# bridge.net
KiCad netlist of a schematic drawn in Altium Designer
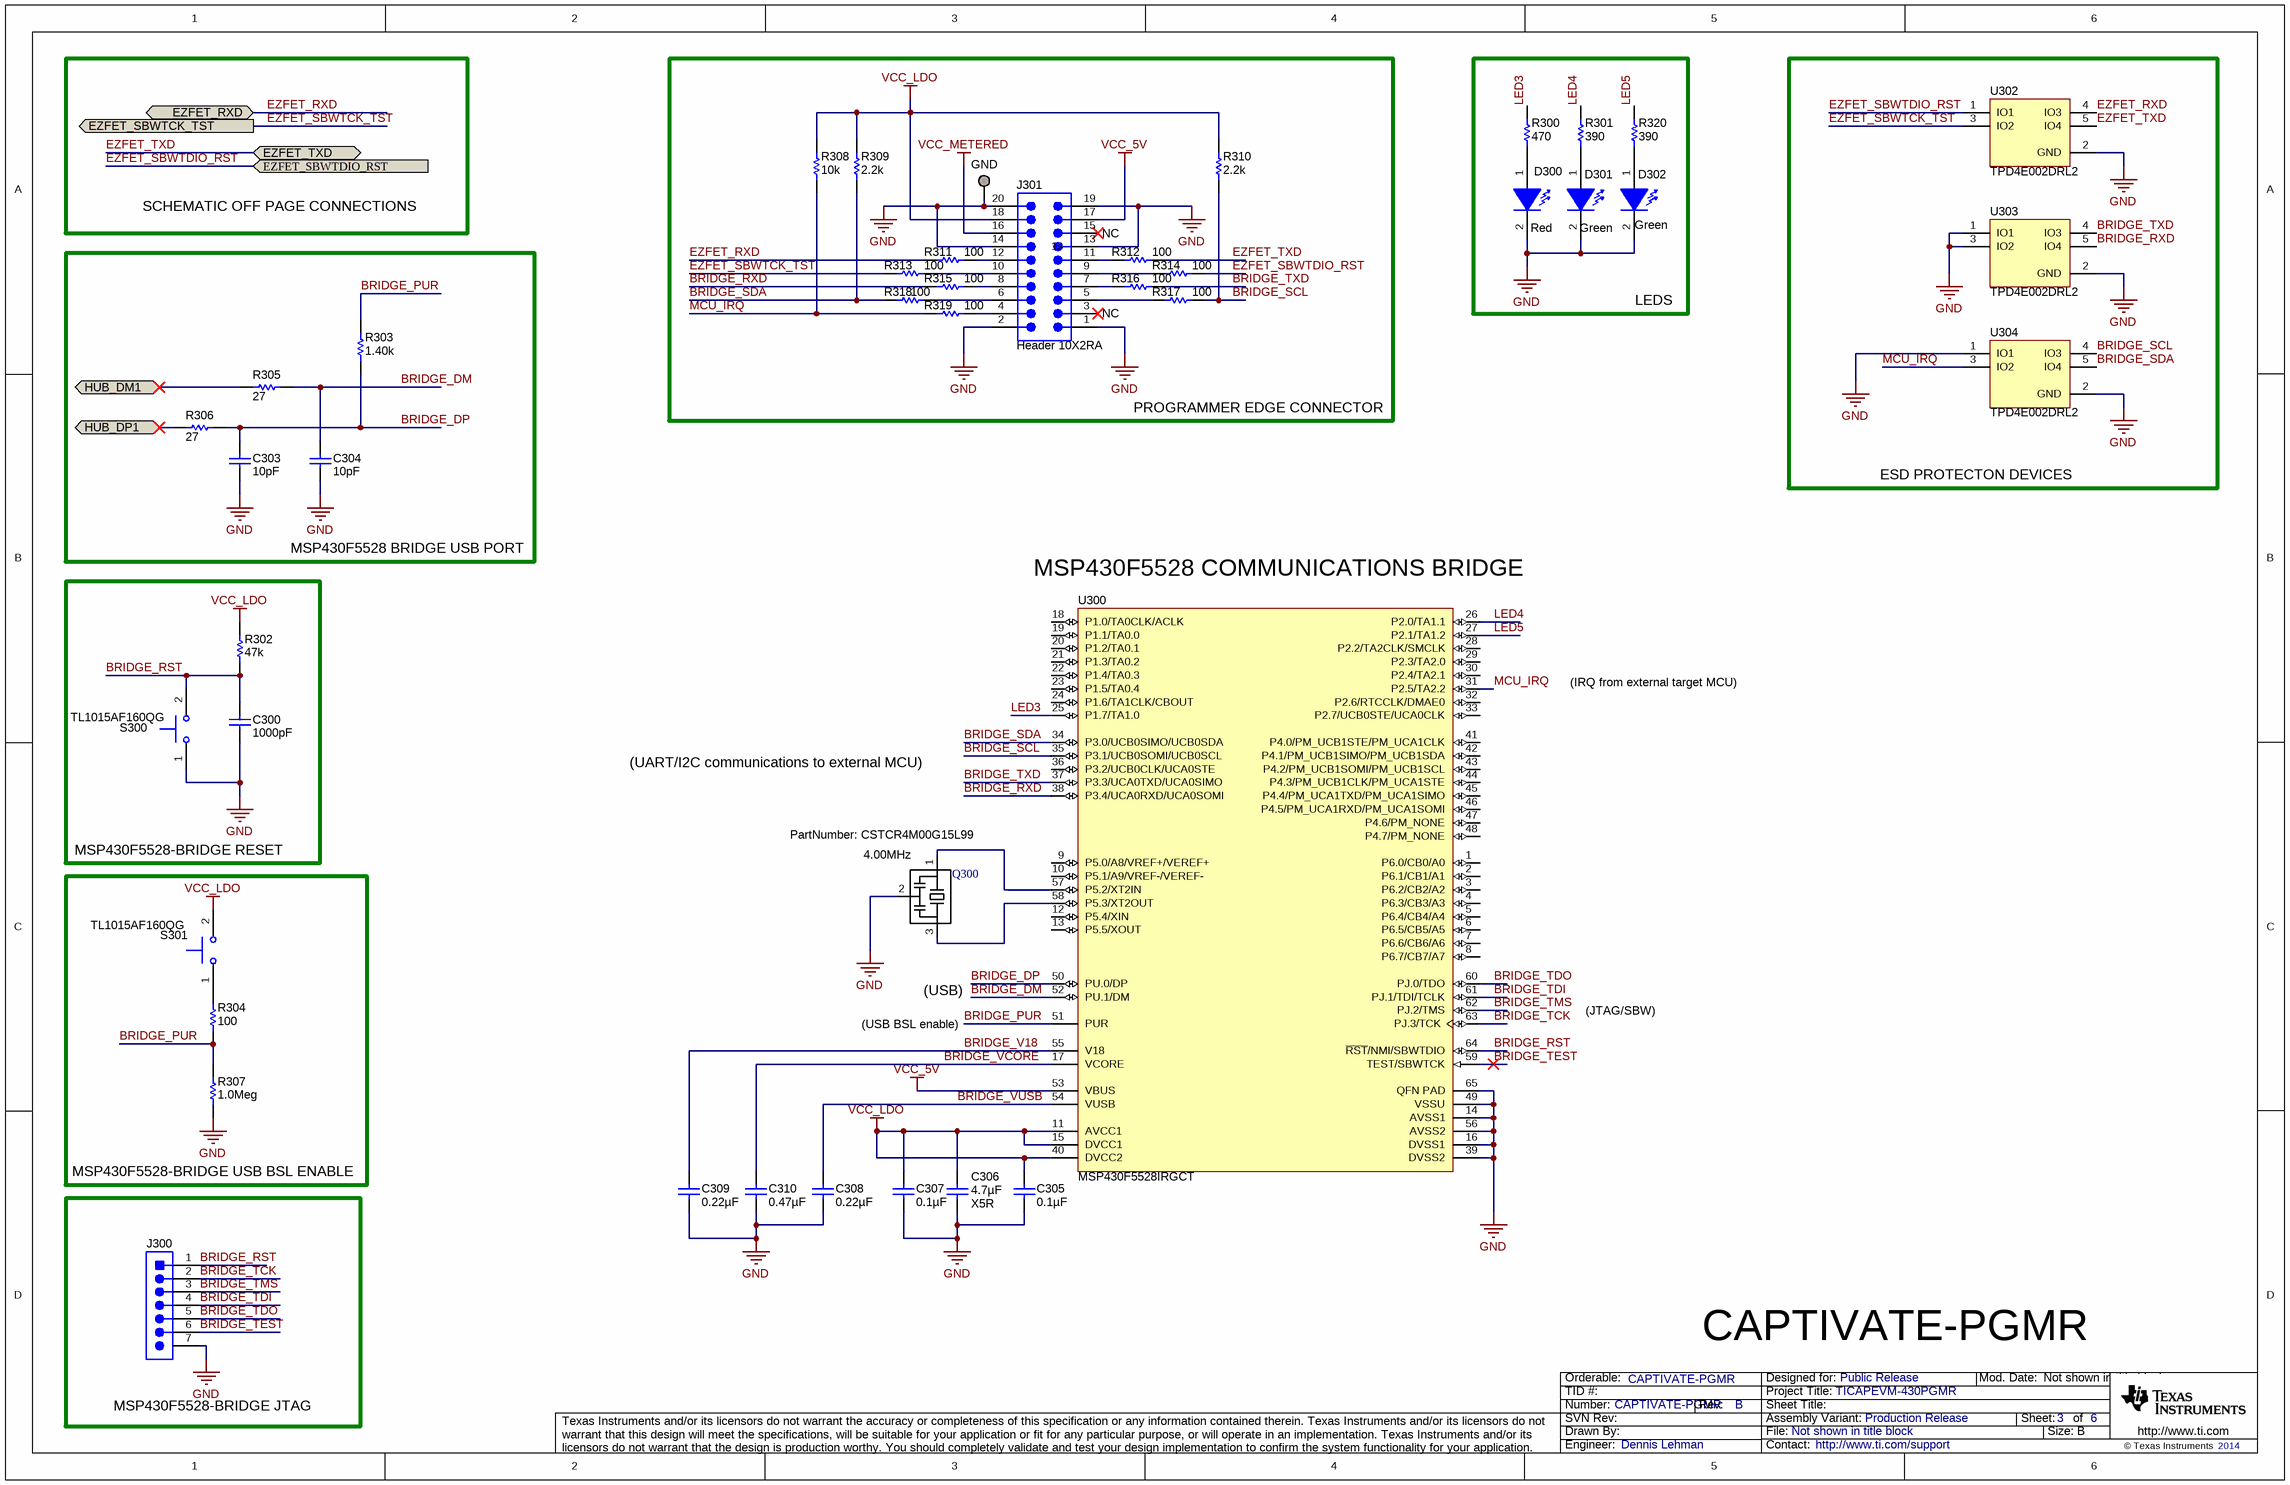
[diagram p0: bridge.SchDoc]

(export (version "E")
  (design (tool "Eeschema 10.0.6"))
  (components
    (comp (ref "C300")
      (value "C1005X7R1H102K")
      (footprint "0402")
      (description "CAP, CERM, 1000pF, 50V, +/-10%, X7R, 0402")
      (fields
        (field (name "VALUEDISPLAYED") "1000pF")
        (field (name "MANUFACTURER") "TDK")
        (field (name "PUBLISHER") "Texas Instruments")
      )
      (libsource (lib "Capacitor_Ceramic") (part "C1005X7R1H102K"))
    )
    (comp (ref "C303")
      (value "GRM1555C1H100JA01D")
      (footprint "0402")
      (description "CAP, CERM, 10pF, 50V, +/-5%, C0G/NP0, 0402")
      (fields
        (field (name "VALUEDISPLAYED") "10pF")
        (field (name "MANUFACTURER") "MuRata")
        (field (name "PUBLISHER") "Texas Instruments")
      )
      (libsource (lib "Capacitor_Ceramic") (part "GRM1555C1H100JA01D"))
    )
    (comp (ref "C304")
      (value "GRM1555C1H100JA01D")
      (footprint "0402")
      (description "CAP, CERM, 10pF, 50V, +/-5%, C0G/NP0, 0402")
      (fields
        (field (name "VALUEDISPLAYED") "10pF")
        (field (name "MANUFACTURER") "MuRata")
        (field (name "PUBLISHER") "Texas Instruments")
      )
      (libsource (lib "Capacitor_Ceramic") (part "GRM1555C1H100JA01D"))
    )
    (comp (ref "C305")
      (value "GRM155R61C104KA88D")
      (footprint "0402")
      (description "CAP, CERM, 0.1uF, 16V, +/-10%, X5R, 0402")
      (fields
        (field (name "VALUEDISPLAYED") "0.1µF")
        (field (name "MANUFACTURER") "MuRata")
        (field (name "PUBLISHER") "Texas Instruments")
      )
      (libsource (lib "Capacitor_Ceramic") (part "GRM155R61C104KA88D"))
    )
    (comp (ref "C306")
      (value "CGB3B1X5R1A475K055AC")
      (footprint "0603")
      (description "CAP, CERM, 4.7 µF, 10 V, +/- 10%, X5R, 0603")
      (fields
        (field (name "VALUEDISPLAYED") "4.7µF")
        (field (name "MANUFACTURER") "TDK")
        (field (name "TEMPCO") "X5R")
        (field (name "PUBLISHER") "Texas Instruments")
      )
      (libsource (lib "Capacitor_Ceramic") (part "CGB3B1X5R1A475K055AC"))
    )
    (comp (ref "C307")
      (value "GRM155R61C104KA88D")
      (footprint "0402")
      (description "CAP, CERM, 0.1uF, 16V, +/-10%, X5R, 0402")
      (fields
        (field (name "VALUEDISPLAYED") "0.1µF")
        (field (name "MANUFACTURER") "MuRata")
        (field (name "PUBLISHER") "Texas Instruments")
      )
      (libsource (lib "Capacitor_Ceramic") (part "GRM155R61C104KA88D"))
    )
    (comp (ref "C308")
      (value "GRM155R61A224KE19D")
      (footprint "0402")
      (description "CAP, CERM, 0.22uF, 10V, +/-10%, X5R, 0402")
      (fields
        (field (name "VALUEDISPLAYED") "0.22µF")
        (field (name "MANUFACTURER") "MuRata")
        (field (name "PUBLISHER") "Texas Instruments")
      )
      (libsource (lib "Capacitor_Ceramic") (part "GRM155R61A224KE19D"))
    )
    (comp (ref "C309")
      (value "GRM155R61A224KE19D")
      (footprint "0402")
      (description "CAP, CERM, 0.22uF, 10V, +/-10%, X5R, 0402")
      (fields
        (field (name "VALUEDISPLAYED") "0.22µF")
        (field (name "MANUFACTURER") "MuRata")
        (field (name "PUBLISHER") "Texas Instruments")
      )
      (libsource (lib "Capacitor_Ceramic") (part "GRM155R61A224KE19D"))
    )
    (comp (ref "C310")
      (value "GRM155R61A474KE15D")
      (footprint "0402")
      (description "CAP, CERM, 0.47uF, 10V, +/-10%, X5R, 0402")
      (fields
        (field (name "VALUEDISPLAYED") "0.47µF")
        (field (name "MANUFACTURER") "MuRata")
        (field (name "PUBLISHER") "Texas Instruments")
      )
      (libsource (lib "Capacitor_Ceramic") (part "GRM155R61A474KE15D"))
    )
    (comp (ref "D300")
      (value "Red")
      (footprint "LED_LTST-C190_Red")
      (description "LED, Red, SMD")
      (fields
        (field (name "MANUFACTURER") "Lite-On")
        (field (name "PARTNUMBER") "LTST-C190CKT")
        (field (name "PUBLISHER") "Texas Instruments")
      )
      (libsource (lib "LED") (part "LTST-C190CKT"))
    )
    (comp (ref "D301")
      (value "Green")
      (footprint "LED_LTST-C190")
      (description "LED, Green, SMD")
      (fields
        (field (name "MANUFACTURER") "Lite-On")
        (field (name "PARTNUMBER") "LTST-C190GKT")
        (field (name "PUBLISHER") "Texas Instruments")
      )
      (libsource (lib "LED") (part "LTST-C190GKT"))
    )
    (comp (ref "D302")
      (value "Green")
      (footprint "LED_LTST-C190")
      (description "LED, Green, SMD")
      (fields
        (field (name "MANUFACTURER") "Lite-On")
        (field (name "PARTNUMBER") "LTST-C190GKT")
        (field (name "PUBLISHER") "Texas Instruments")
      )
      (libsource (lib "LED") (part "LTST-C190GKT"))
    )
    (comp (ref "GND")
      (value "TESTPOINT")
      (footprint "TP_VIA_060RND040")
      (description "TEST POINT.  No entry in BOM.")
      (fields (field (name "PUBLISHER") "Texas Instruments"))
      (libsource (lib "MiscParts") (part "TESTPOINT"))
    )
    (comp (ref "J300")
      (value "GRPB071VWVN-RC")
      (footprint "Sullins_GRPB071VWVN-RC")
      (description "Header, 50mil, 7x1, Gold,  TH")
      (fields
        (field (name "MANUFACTURER") "Sullins Connector Solutions")
        (field (name "PUBLISHER") "Texas Instruments")
      )
      (libsource (lib "Captivate Library") (part "GRPB071VWVN-RC"))
    )
    (comp (ref "J301")
      (value "Header 10X2RA")
      (footprint "HDR2X10RA")
      (description "Header, Male, 10-Pin, 2 row, Shround, Right Angle")
      (fields
        (field (name "MANUFACTURER") "Samtec")
        (field (name "PARTNUMBER") "TSSH-110-01-L-D-RA")
        (field (name "PUBLISHER") "Altium Limited")
      )
      (libsource (lib "Captivate Library") (part "Header 10X2RA"))
    )
    (comp (ref "Q300")
      (value "RATA-FILTER_CSTCR4M00G15")
      (footprint "CSTCR CERAMIC RESONATOR - MURATA")
      (description "4.00MHz resonator")
      (fields (field (name "VALUE DISPLAYED") "4.00MHz") (field (name "PARTNUMBER") "CSTCR4M00G15L99"))
      (libsource (lib "Captivate Library") (part "MURATA-FILTER_CSTCR4M00G15"))
    )
    (comp (ref "R300")
      (value "470")
      (footprint "0402")
      (description "RES, 470 ohm, 5%, 0.063W, 0402")
      (fields
        (field (name "PARTNUMBER") "CRCW0402470RJNED")
        (field (name "MANUFACTURER") "Vishay-Dale")
        (field (name "PUBLISHER") "Texas Instruments")
      )
      (libsource (lib "Resistor_0402") (part "CRCW0402470RJNED"))
    )
    (comp (ref "R301")
      (value "390")
      (footprint "0402")
      (description "RES, 390 ohm, 5%, 0.063W, 0402")
      (fields
        (field (name "PARTNUMBER") "CRCW0402390RJNED")
        (field (name "MANUFACTURER") "Vishay-Dale")
        (field (name "PUBLISHER") "Texas Instruments")
      )
      (libsource (lib "Resistor_0402") (part "CRCW0402390RJNED"))
    )
    (comp (ref "R302")
      (value "47k")
      (footprint "0402")
      (description "RES, 47k ohm, 5%, 0.063W, 0402")
      (fields
        (field (name "PARTNUMBER") "CRCW040247K0JNED")
        (field (name "MANUFACTURER") "Vishay-Dale")
        (field (name "PUBLISHER") "Texas Instruments")
      )
      (libsource (lib "Resistor_0402") (part "CRCW040247K0JNED"))
    )
    (comp (ref "R303")
      (value "1.40k")
      (footprint "0402")
      (description "RES, 1.40k ohm, 1%, 0.063W, 0402")
      (fields
        (field (name "PARTNUMBER") "CRCW04021K40FKED")
        (field (name "MANUFACTURER") "Vishay-Dale")
        (field (name "PUBLISHER") "Texas Instruments")
      )
      (libsource (lib "Resistor_0402") (part "CRCW04021K40FKED"))
    )
    (comp (ref "R304")
      (value "100")
      (footprint "0402")
      (description "RES, 100 ohm, 5%, 0.063W, 0402")
      (fields
        (field (name "PARTNUMBER") "CRCW0402100RJNED")
        (field (name "MANUFACTURER") "Vishay-Dale")
        (field (name "PUBLISHER") "Texas Instruments")
      )
      (libsource (lib "Resistor_0402") (part "CRCW0402100RJNED"))
    )
    (comp (ref "R305")
      (value "27")
      (footprint "0402")
      (description "RES, 27 ohm, 5%, 0.063W, 0402")
      (fields
        (field (name "PARTNUMBER") "CRCW040227R0JNED")
        (field (name "MANUFACTURER") "Vishay-Dale")
        (field (name "PUBLISHER") "Texas Instruments")
      )
      (libsource (lib "Resistor_0402") (part "CRCW040227R0JNED"))
    )
    (comp (ref "R306")
      (value "27")
      (footprint "0402")
      (description "RES, 27 ohm, 5%, 0.063W, 0402")
      (fields
        (field (name "PARTNUMBER") "CRCW040227R0JNED")
        (field (name "MANUFACTURER") "Vishay-Dale")
        (field (name "PUBLISHER") "Texas Instruments")
      )
      (libsource (lib "Resistor_0402") (part "CRCW040227R0JNED"))
    )
    (comp (ref "R307")
      (value "1.0Meg")
      (footprint "0402")
      (description "RES, 1.0Meg ohm, 5%, 0.063W, 0402")
      (fields
        (field (name "PARTNUMBER") "CRCW04021M00JNED")
        (field (name "MANUFACTURER") "Vishay-Dale")
        (field (name "PUBLISHER") "Texas Instruments")
      )
      (libsource (lib "Resistor_0402") (part "CRCW04021M00JNED"))
    )
    (comp (ref "R308")
      (value "CRCW040210K0JNED")
      (footprint "0402")
      (description "RES, 10 k, 5%, 0.063 W, 0402")
      (fields
        (field (name "VALUEDISPLAYED") "10k")
        (field (name "MANUFACTURER") "Vishay-Dale")
        (field (name "PUBLISHER") "Texas Instruments")
      )
      (libsource (lib "Resistor_0402") (part "CRCW040210K0JNED"))
    )
    (comp (ref "R309")
      (value "CRCW04022K20JNED")
      (footprint "0402")
      (description "RES, 2.2 k, 5%, 0.063 W, 0402")
      (fields
        (field (name "VALUEDISPLAYED") "2.2k")
        (field (name "MANUFACTURER") "Vishay-Dale")
        (field (name "PUBLISHER") "Texas Instruments")
      )
      (libsource (lib "Resistor_0402") (part "CRCW04022K20JNED"))
    )
    (comp (ref "R310")
      (value "CRCW04022K20JNED")
      (footprint "0402")
      (description "RES, 2.2 k, 5%, 0.063 W, 0402")
      (fields
        (field (name "VALUEDISPLAYED") "2.2k")
        (field (name "MANUFACTURER") "Vishay-Dale")
        (field (name "PUBLISHER") "Texas Instruments")
      )
      (libsource (lib "Resistor_0402") (part "CRCW04022K20JNED"))
    )
    (comp (ref "R311")
      (value "CRCW0402100RJNED")
      (footprint "0402")
      (description "RES, 100, 5%, 0.063 W, 0402")
      (fields
        (field (name "VALUEDISPLAYED") "100")
        (field (name "MANUFACTURER") "Vishay-Dale")
        (field (name "PUBLISHER") "Texas Instruments")
      )
      (libsource (lib "Resistor_0402") (part "CRCW0402100RJNED"))
    )
    (comp (ref "R312")
      (value "CRCW0402100RJNED")
      (footprint "0402")
      (description "RES, 100, 5%, 0.063 W, 0402")
      (fields
        (field (name "VALUEDISPLAYED") "100")
        (field (name "MANUFACTURER") "Vishay-Dale")
        (field (name "PUBLISHER") "Texas Instruments")
      )
      (libsource (lib "Resistor_0402") (part "CRCW0402100RJNED"))
    )
    (comp (ref "R313")
      (value "CRCW0402100RJNED")
      (footprint "0402")
      (description "RES, 100, 5%, 0.063 W, 0402")
      (fields
        (field (name "VALUEDISPLAYED") "100")
        (field (name "MANUFACTURER") "Vishay-Dale")
        (field (name "PUBLISHER") "Texas Instruments")
      )
      (libsource (lib "Resistor_0402") (part "CRCW0402100RJNED"))
    )
    (comp (ref "R314")
      (value "CRCW0402100RJNED")
      (footprint "0402")
      (description "RES, 100, 5%, 0.063 W, 0402")
      (fields
        (field (name "VALUEDISPLAYED") "100")
        (field (name "MANUFACTURER") "Vishay-Dale")
        (field (name "PUBLISHER") "Texas Instruments")
      )
      (libsource (lib "Resistor_0402") (part "CRCW0402100RJNED"))
    )
    (comp (ref "R315")
      (value "CRCW0402100RJNED")
      (footprint "0402")
      (description "RES, 100, 5%, 0.063 W, 0402")
      (fields
        (field (name "VALUEDISPLAYED") "100")
        (field (name "MANUFACTURER") "Vishay-Dale")
        (field (name "PUBLISHER") "Texas Instruments")
      )
      (libsource (lib "Resistor_0402") (part "CRCW0402100RJNED"))
    )
    (comp (ref "R316")
      (value "CRCW0402100RJNED")
      (footprint "0402")
      (description "RES, 100, 5%, 0.063 W, 0402")
      (fields
        (field (name "VALUEDISPLAYED") "100")
        (field (name "MANUFACTURER") "Vishay-Dale")
        (field (name "PUBLISHER") "Texas Instruments")
      )
      (libsource (lib "Resistor_0402") (part "CRCW0402100RJNED"))
    )
    (comp (ref "R317")
      (value "CRCW0402100RJNED")
      (footprint "0402")
      (description "RES, 100, 5%, 0.063 W, 0402")
      (fields
        (field (name "VALUEDISPLAYED") "100")
        (field (name "MANUFACTURER") "Vishay-Dale")
        (field (name "PUBLISHER") "Texas Instruments")
      )
      (libsource (lib "Resistor_0402") (part "CRCW0402100RJNED"))
    )
    (comp (ref "R318")
      (value "CRCW0402100RJNED")
      (footprint "0402")
      (description "RES, 100, 5%, 0.063 W, 0402")
      (fields
        (field (name "VALUEDISPLAYED") "100")
        (field (name "MANUFACTURER") "Vishay-Dale")
        (field (name "PUBLISHER") "Texas Instruments")
      )
      (libsource (lib "Resistor_0402") (part "CRCW0402100RJNED"))
    )
    (comp (ref "R319")
      (value "CRCW0402100RJNED")
      (footprint "0402")
      (description "RES, 100, 5%, 0.063 W, 0402")
      (fields
        (field (name "VALUEDISPLAYED") "100")
        (field (name "MANUFACTURER") "Vishay-Dale")
        (field (name "PUBLISHER") "Texas Instruments")
      )
      (libsource (lib "Resistor_0402") (part "CRCW0402100RJNED"))
    )
    (comp (ref "R320")
      (value "390")
      (footprint "0402")
      (description "RES, 390 ohm, 5%, 0.063W, 0402")
      (fields
        (field (name "PARTNUMBER") "CRCW0402390RJNED")
        (field (name "MANUFACTURER") "Vishay-Dale")
        (field (name "PUBLISHER") "Texas Instruments")
      )
      (libsource (lib "Resistor_0402") (part "CRCW0402390RJNED"))
    )
    (comp (ref "S300")
      (value "TL1015AF160QG")
      (footprint "SW_TL1015AF160QG")
      (description "Switch, Tactile, SPST-NO, 0.05A, 12V, SMT")
      (fields
        (field (name "MANUFACTURER") "E-Switch")
        (field (name "SYMBOLCREATOR") "a0412235")
        (field (name "PUBLISHER") "Texas Instruments")
      )
      (libsource (lib "Switches") (part "TL1015AF160QG"))
    )
    (comp (ref "S301")
      (value "TL1015AF160QG")
      (footprint "SW_TL1015AF160QG")
      (description "Switch, Tactile, SPST-NO, 0.05A, 12V, SMT")
      (fields
        (field (name "MANUFACTURER") "E-Switch")
        (field (name "SYMBOLCREATOR") "a0412235")
        (field (name "PUBLISHER") "Texas Instruments")
      )
      (libsource (lib "Switches") (part "TL1015AF160QG"))
    )
    (comp (ref "U300")
      (value "MSP430F5528IRGCT")
      (footprint "RGC0064B")
      (fields (field (name "MANUFACTURER") "Texas Instruments"))
      (libsource (lib "TI MCU MSP430") (part "MSP430F5528IRGCT"))
    )
    (comp (ref "U302")
      (value "TPD4E002DRL2")
      (footprint "DRL0005A")
      (fields
        (field (name "MANUFACTURER") "Texas Instruments")
        (field (name "ALTERNATE PARTNUMBER") "Equivalent")
      )
      (libsource (lib "TI Interface ESD EMI Protection") (part "TPD4E002DRL2"))
    )
    (comp (ref "U303")
      (value "TPD4E002DRL2")
      (footprint "DRL0005A")
      (fields
        (field (name "MANUFACTURER") "Texas Instruments")
        (field (name "ALTERNATE PARTNUMBER") "Equivalent")
      )
      (libsource (lib "TI Interface ESD EMI Protection") (part "TPD4E002DRL2"))
    )
    (comp (ref "U304")
      (value "TPD4E002DRL2")
      (footprint "DRL0005A")
      (fields
        (field (name "MANUFACTURER") "Texas Instruments")
        (field (name "ALTERNATE PARTNUMBER") "Equivalent")
      )
      (libsource (lib "TI Interface ESD EMI Protection") (part "TPD4E002DRL2"))
    )
  )
  (nets
    (net (code "1") (name "/BRIDGE_DM") (class "Default")
      (node (ref "C304") (pin "1") (pinfunction "1_1") (pintype "passive"))
      (node (ref "R305") (pin "2") (pinfunction "2_2") (pintype "passive"))
      (node (ref "U300") (pin "52") (pinfunction "PU.1/DM_52") (pintype "bidirectional"))
    )
    (net (code "2") (name "/BRIDGE_DP") (class "Default")
      (node (ref "C303") (pin "1") (pinfunction "1_1") (pintype "passive"))
      (node (ref "R303") (pin "1") (pinfunction "1_1") (pintype "passive"))
      (node (ref "R306") (pin "2") (pinfunction "2_2") (pintype "passive"))
      (node (ref "U300") (pin "50") (pinfunction "PU.0/DP_50") (pintype "bidirectional"))
    )
    (net (code "3") (name "/BRIDGE_PUR") (class "Default")
      (node (ref "R303") (pin "2") (pinfunction "2_2") (pintype "passive"))
      (node (ref "R304") (pin "1") (pinfunction "1_1") (pintype "passive"))
      (node (ref "R307") (pin "2") (pinfunction "2_2") (pintype "passive"))
      (node (ref "U300") (pin "51") (pinfunction "PUR_51") (pintype "passive"))
    )
    (net (code "4") (name "/BRIDGE_RST") (class "Default")
      (node (ref "C300") (pin "1") (pinfunction "1_1") (pintype "passive"))
      (node (ref "J300") (pin "1") (pinfunction "1_1") (pintype "passive"))
      (node (ref "R302") (pin "1") (pinfunction "1_1") (pintype "passive"))
      (node (ref "S300") (pin "2") (pinfunction "2_2") (pintype "passive"))
      (node (ref "U300") (pin "64") (pinfunction "~{RST}/NMI/SBWTDIO_64") (pintype "bidirectional"))
    )
    (net (code "5") (name "/BRIDGE_RXD") (class "Default")
      (node (ref "R315") (pin "1") (pinfunction "1_1") (pintype "passive"))
      (node (ref "U300") (pin "38") (pinfunction "P3.4/UCA0RXD/UCA0SOMI_38") (pintype "bidirectional"))
      (node (ref "U303") (pin "5") (pinfunction "IO4_5") (pintype "passive"))
    )
    (net (code "6") (name "/BRIDGE_SCL") (class "Default")
      (node (ref "R310") (pin "2") (pinfunction "2_2") (pintype "passive"))
      (node (ref "R317") (pin "2") (pinfunction "2_2") (pintype "passive"))
      (node (ref "U300") (pin "35") (pinfunction "P3.1/UCB0SOMI/UCB0SCL_35") (pintype "bidirectional"))
      (node (ref "U304") (pin "4") (pinfunction "IO3_4") (pintype "passive"))
    )
    (net (code "7") (name "/BRIDGE_SDA") (class "Default")
      (node (ref "R309") (pin "1") (pinfunction "1_1") (pintype "passive"))
      (node (ref "R318") (pin "1") (pinfunction "1_1") (pintype "passive"))
      (node (ref "U300") (pin "34") (pinfunction "P3.0/UCB0SIMO/UCB0SDA_34") (pintype "bidirectional"))
      (node (ref "U304") (pin "5") (pinfunction "IO4_5") (pintype "passive"))
    )
    (net (code "8") (name "/BRIDGE_TCK") (class "Default")
      (node (ref "J300") (pin "2") (pinfunction "2_2") (pintype "passive"))
      (node (ref "U300") (pin "63") (pinfunction "PJ.3/TCK_63") (pintype "bidirectional"))
    )
    (net (code "9") (name "/BRIDGE_TDI") (class "Default")
      (node (ref "J300") (pin "4") (pinfunction "4_4") (pintype "passive"))
      (node (ref "U300") (pin "61") (pinfunction "PJ.1/TDI/TCLK_61") (pintype "bidirectional"))
    )
    (net (code "10") (name "/BRIDGE_TDO") (class "Default")
      (node (ref "J300") (pin "5") (pinfunction "5_5") (pintype "passive"))
      (node (ref "U300") (pin "60") (pinfunction "PJ.0/TDO_60") (pintype "bidirectional"))
    )
    (net (code "11") (name "/BRIDGE_TEST") (class "Default")
      (node (ref "J300") (pin "6") (pinfunction "6_6") (pintype "passive"))
      (node (ref "U300") (pin "59") (pinfunction "TEST/SBWTCK_59") (pintype "input"))
    )
    (net (code "12") (name "/BRIDGE_TMS") (class "Default")
      (node (ref "J300") (pin "3") (pinfunction "3_3") (pintype "passive"))
      (node (ref "U300") (pin "62") (pinfunction "PJ.2/TMS_62") (pintype "bidirectional"))
    )
    (net (code "13") (name "/BRIDGE_TXD") (class "Default")
      (node (ref "R316") (pin "2") (pinfunction "2_2") (pintype "passive"))
      (node (ref "U300") (pin "37") (pinfunction "P3.3/UCA0TXD/UCA0SIMO_37") (pintype "bidirectional"))
      (node (ref "U303") (pin "4") (pinfunction "IO3_4") (pintype "passive"))
    )
    (net (code "14") (name "/BRIDGE_V18") (class "Default")
      (node (ref "C309") (pin "1") (pinfunction "1_1") (pintype "passive"))
      (node (ref "U300") (pin "55") (pinfunction "V18_55") (pintype "passive"))
    )
    (net (code "15") (name "/BRIDGE_VCORE") (class "Default")
      (node (ref "C310") (pin "1") (pinfunction "1_1") (pintype "passive"))
      (node (ref "U300") (pin "17") (pinfunction "VCORE_17") (pintype "passive"))
    )
    (net (code "16") (name "/BRIDGE_VUSB") (class "Default")
      (node (ref "C308") (pin "1") (pinfunction "1_1") (pintype "passive"))
      (node (ref "U300") (pin "54") (pinfunction "VUSB_54") (pintype "power_in"))
    )
    (net (code "17") (name "/EZFET_RXD") (class "Default")
      (node (ref "R311") (pin "1") (pinfunction "1_1") (pintype "passive"))
      (node (ref "U302") (pin "4") (pinfunction "IO3_4") (pintype "passive"))
    )
    (net (code "18") (name "/EZFET_SBWTCK_TST") (class "Default")
      (node (ref "R313") (pin "1") (pinfunction "1_1") (pintype "passive"))
      (node (ref "U302") (pin "3") (pinfunction "IO2_3") (pintype "passive"))
    )
    (net (code "19") (name "/EZFET_SBWTDIO_RST") (class "Default")
      (node (ref "R314") (pin "2") (pinfunction "2_2") (pintype "passive"))
      (node (ref "U302") (pin "1") (pinfunction "IO1_1") (pintype "passive"))
    )
    (net (code "20") (name "/EZFET_TXD") (class "Default")
      (node (ref "R312") (pin "2") (pinfunction "2_2") (pintype "passive"))
      (node (ref "U302") (pin "5") (pinfunction "IO4_5") (pintype "passive"))
    )
    (net (code "21") (name "/HUB_DM1") (class "Default")
      (node (ref "R305") (pin "1") (pinfunction "1_1") (pintype "passive+no_connect"))
    )
    (net (code "22") (name "/HUB_DP1") (class "Default")
      (node (ref "R306") (pin "1") (pinfunction "1_1") (pintype "passive+no_connect"))
    )
    (net (code "23") (name "/LED3") (class "Default")
      (node (ref "R300") (pin "2") (pinfunction "2_2") (pintype "passive"))
      (node (ref "U300") (pin "25") (pinfunction "P1.7/TA1.0_25") (pintype "bidirectional"))
    )
    (net (code "24") (name "/LED4") (class "Default")
      (node (ref "R301") (pin "2") (pinfunction "2_2") (pintype "passive"))
      (node (ref "U300") (pin "26") (pinfunction "P2.0/TA1.1_26") (pintype "bidirectional"))
    )
    (net (code "25") (name "/LED5") (class "Default")
      (node (ref "R320") (pin "2") (pinfunction "2_2") (pintype "passive"))
      (node (ref "U300") (pin "27") (pinfunction "P2.1/TA1.2_27") (pintype "bidirectional"))
    )
    (net (code "26") (name "/MCU_IRQ") (class "Default")
      (node (ref "R308") (pin "1") (pinfunction "1_1") (pintype "passive"))
      (node (ref "R319") (pin "1") (pinfunction "1_1") (pintype "passive"))
      (node (ref "U300") (pin "31") (pinfunction "P2.5/TA2.2_31") (pintype "bidirectional"))
      (node (ref "U304") (pin "3") (pinfunction "IO2_3") (pintype "passive"))
    )
    (net (code "27") (name "GND") (class "Default")
      (node (ref "C300") (pin "2") (pinfunction "2_2") (pintype "passive"))
      (node (ref "C303") (pin "2") (pinfunction "2_2") (pintype "passive"))
      (node (ref "C304") (pin "2") (pinfunction "2_2") (pintype "passive"))
      (node (ref "C305") (pin "2") (pinfunction "2_2") (pintype "passive"))
      (node (ref "C306") (pin "2") (pinfunction "2_2") (pintype "passive"))
      (node (ref "C307") (pin "2") (pinfunction "2_2") (pintype "passive"))
      (node (ref "C308") (pin "2") (pinfunction "2_2") (pintype "passive"))
      (node (ref "C309") (pin "2") (pinfunction "2_2") (pintype "passive"))
      (node (ref "C310") (pin "2") (pinfunction "2_2") (pintype "passive"))
      (node (ref "D300") (pin "2") (pinfunction "K_2") (pintype "passive"))
      (node (ref "D301") (pin "2") (pinfunction "K_2") (pintype "passive"))
      (node (ref "D302") (pin "2") (pinfunction "K_2") (pintype "passive"))
      (node (ref "GND") (pin "1") (pintype "passive"))
      (node (ref "J300") (pin "7") (pinfunction "7_7") (pintype "passive"))
      (node (ref "J301") (pin "1") (pinfunction "1_1") (pintype "passive"))
      (node (ref "J301") (pin "13") (pinfunction "13_13") (pintype "passive"))
      (node (ref "J301") (pin "14") (pinfunction "14_14") (pintype "passive"))
      (node (ref "J301") (pin "19") (pinfunction "19_19") (pintype "passive"))
      (node (ref "J301") (pin "2") (pinfunction "2_2") (pintype "passive"))
      (node (ref "J301") (pin "20") (pinfunction "20_20") (pintype "passive"))
      (node (ref "Q300") (pin "2") (pinfunction "2_2") (pintype "passive"))
      (node (ref "R307") (pin "1") (pinfunction "1_1") (pintype "passive"))
      (node (ref "S300") (pin "1") (pinfunction "1_1") (pintype "passive"))
      (node (ref "U300") (pin "14") (pinfunction "AVSS1_14") (pintype "power_in"))
      (node (ref "U300") (pin "16") (pinfunction "DVSS1_16") (pintype "power_in"))
      (node (ref "U300") (pin "39") (pinfunction "DVSS2_39") (pintype "power_in"))
      (node (ref "U300") (pin "49") (pinfunction "VSSU_49") (pintype "power_in"))
      (node (ref "U300") (pin "56") (pinfunction "AVSS2_56") (pintype "power_in"))
      (node (ref "U300") (pin "65") (pinfunction "QFN_PAD_65") (pintype "power_in"))
      (node (ref "U302") (pin "2") (pinfunction "GND_2") (pintype "power_in"))
      (node (ref "U303") (pin "1") (pinfunction "IO1_1") (pintype "passive"))
      (node (ref "U303") (pin "2") (pinfunction "GND_2") (pintype "power_in"))
      (node (ref "U303") (pin "3") (pinfunction "IO2_3") (pintype "passive"))
      (node (ref "U304") (pin "1") (pinfunction "IO1_1") (pintype "passive"))
      (node (ref "U304") (pin "2") (pinfunction "GND_2") (pintype "power_in"))
    )
    (net (code "28") (name "Net-(D300-A)") (class "Default")
      (node (ref "D300") (pin "1") (pinfunction "A_1") (pintype "passive"))
      (node (ref "R300") (pin "1") (pinfunction "1_1") (pintype "passive"))
    )
    (net (code "29") (name "Net-(D301-A)") (class "Default")
      (node (ref "D301") (pin "1") (pinfunction "A_1") (pintype "passive"))
      (node (ref "R301") (pin "1") (pinfunction "1_1") (pintype "passive"))
    )
    (net (code "30") (name "Net-(D302-A)") (class "Default")
      (node (ref "D302") (pin "1") (pinfunction "A_1") (pintype "passive"))
      (node (ref "R320") (pin "1") (pinfunction "1_1") (pintype "passive"))
    )
    (net (code "31") (name "Net-(J301-Pad4)") (class "Default")
      (node (ref "J301") (pin "4") (pinfunction "4_4") (pintype "passive"))
      (node (ref "R319") (pin "2") (pinfunction "2_2") (pintype "passive"))
    )
    (net (code "32") (name "Net-(J301-Pad5)") (class "Default")
      (node (ref "J301") (pin "5") (pinfunction "5_5") (pintype "passive"))
      (node (ref "R317") (pin "1") (pinfunction "1_1") (pintype "passive"))
    )
    (net (code "33") (name "Net-(J301-Pad6)") (class "Default")
      (node (ref "J301") (pin "6") (pinfunction "6_6") (pintype "passive"))
      (node (ref "R318") (pin "2") (pinfunction "2_2") (pintype "passive"))
    )
    (net (code "34") (name "Net-(J301-Pad7)") (class "Default")
      (node (ref "J301") (pin "7") (pinfunction "7_7") (pintype "passive"))
      (node (ref "R316") (pin "1") (pinfunction "1_1") (pintype "passive"))
    )
    (net (code "35") (name "Net-(J301-Pad8)") (class "Default")
      (node (ref "J301") (pin "8") (pinfunction "8_8") (pintype "passive"))
      (node (ref "R315") (pin "2") (pinfunction "2_2") (pintype "passive"))
    )
    (net (code "36") (name "Net-(J301-Pad9)") (class "Default")
      (node (ref "J301") (pin "9") (pinfunction "9_9") (pintype "passive"))
      (node (ref "R314") (pin "1") (pinfunction "1_1") (pintype "passive"))
    )
    (net (code "37") (name "Net-(J301-Pad10)") (class "Default")
      (node (ref "J301") (pin "10") (pinfunction "10_10") (pintype "passive"))
      (node (ref "R313") (pin "2") (pinfunction "2_2") (pintype "passive"))
    )
    (net (code "38") (name "Net-(J301-Pad11)") (class "Default")
      (node (ref "J301") (pin "11") (pinfunction "11_11") (pintype "passive"))
      (node (ref "R312") (pin "1") (pinfunction "1_1") (pintype "passive"))
    )
    (net (code "39") (name "Net-(J301-Pad12)") (class "Default")
      (node (ref "J301") (pin "12") (pinfunction "12_12") (pintype "passive"))
      (node (ref "R311") (pin "2") (pinfunction "2_2") (pintype "passive"))
    )
    (net (code "40") (name "Net-(R304-Pad2)") (class "Default")
      (node (ref "R304") (pin "2") (pinfunction "2_2") (pintype "passive"))
      (node (ref "S301") (pin "1") (pinfunction "1_1") (pintype "passive"))
    )
    (net (code "41") (name "Net-(U300-P5.2{slash}XT2IN)") (class "Default")
      (node (ref "Q300") (pin "1") (pinfunction "1_1") (pintype "passive"))
      (node (ref "U300") (pin "57") (pinfunction "P5.2/XT2IN_57") (pintype "bidirectional"))
    )
    (net (code "42") (name "Net-(U300-P5.3{slash}XT2OUT)") (class "Default")
      (node (ref "Q300") (pin "3") (pinfunction "3_3") (pintype "passive"))
      (node (ref "U300") (pin "58") (pinfunction "P5.3/XT2OUT_58") (pintype "bidirectional"))
    )
    (net (code "43") (name "VCC_5V") (class "Default")
      (node (ref "J301") (pin "17") (pinfunction "17_17") (pintype "passive"))
      (node (ref "U300") (pin "53") (pinfunction "VBUS_53") (pintype "power_in"))
    )
    (net (code "44") (name "VCC_LDO") (class "Default")
      (node (ref "C305") (pin "1") (pinfunction "1_1") (pintype "passive"))
      (node (ref "C306") (pin "1") (pinfunction "1_1") (pintype "passive"))
      (node (ref "C307") (pin "1") (pinfunction "1_1") (pintype "passive"))
      (node (ref "J301") (pin "18") (pinfunction "18_18") (pintype "passive"))
      (node (ref "R302") (pin "2") (pinfunction "2_2") (pintype "passive"))
      (node (ref "R308") (pin "2") (pinfunction "2_2") (pintype "passive"))
      (node (ref "R309") (pin "2") (pinfunction "2_2") (pintype "passive"))
      (node (ref "R310") (pin "1") (pinfunction "1_1") (pintype "passive"))
      (node (ref "S301") (pin "2") (pinfunction "2_2") (pintype "passive"))
      (node (ref "U300") (pin "11") (pinfunction "AVCC1_11") (pintype "power_in"))
      (node (ref "U300") (pin "15") (pinfunction "DVCC1_15") (pintype "power_in"))
      (node (ref "U300") (pin "40") (pinfunction "DVCC2_40") (pintype "power_in"))
    )
    (net (code "45") (name "VCC_METERED") (class "Default")
      (node (ref "J301") (pin "16") (pinfunction "16_16") (pintype "passive"))
    )
    (net (code "46") (name "unconnected-(J301-Pad3)") (class "Default")
      (node (ref "J301") (pin "3") (pinfunction "3_3") (pintype "passive+no_connect"))
    )
    (net (code "47") (name "unconnected-(J301-Pad15)") (class "Default")
      (node (ref "J301") (pin "15") (pinfunction "15_15") (pintype "passive+no_connect"))
    )
    (net (code "48") (name "unconnected-(U300-P1.0{slash}TA0CLK{slash}ACLK-Pad18)") (class "Default")
      (node (ref "U300") (pin "18") (pinfunction "P1.0/TA0CLK/ACLK_18") (pintype "bidirectional"))
    )
    (net (code "49") (name "unconnected-(U300-P1.1{slash}TA0.0-Pad19)") (class "Default")
      (node (ref "U300") (pin "19") (pinfunction "P1.1/TA0.0_19") (pintype "bidirectional"))
    )
    (net (code "50") (name "unconnected-(U300-P1.2{slash}TA0.1-Pad20)") (class "Default")
      (node (ref "U300") (pin "20") (pinfunction "P1.2/TA0.1_20") (pintype "bidirectional"))
    )
    (net (code "51") (name "unconnected-(U300-P1.3{slash}TA0.2-Pad21)") (class "Default")
      (node (ref "U300") (pin "21") (pinfunction "P1.3/TA0.2_21") (pintype "bidirectional"))
    )
    (net (code "52") (name "unconnected-(U300-P1.4{slash}TA0.3-Pad22)") (class "Default")
      (node (ref "U300") (pin "22") (pinfunction "P1.4/TA0.3_22") (pintype "bidirectional"))
    )
    (net (code "53") (name "unconnected-(U300-P1.5{slash}TA0.4-Pad23)") (class "Default")
      (node (ref "U300") (pin "23") (pinfunction "P1.5/TA0.4_23") (pintype "bidirectional"))
    )
    (net (code "54") (name "unconnected-(U300-P1.6{slash}TA1CLK{slash}CBOUT-Pad24)") (class "Default")
      (node (ref "U300") (pin "24") (pinfunction "P1.6/TA1CLK/CBOUT_24") (pintype "bidirectional"))
    )
    (net (code "55") (name "unconnected-(U300-P2.2{slash}TA2CLK{slash}SMCLK-Pad28)") (class "Default")
      (node (ref "U300") (pin "28") (pinfunction "P2.2/TA2CLK/SMCLK_28") (pintype "bidirectional"))
    )
    (net (code "56") (name "unconnected-(U300-P2.3{slash}TA2.0-Pad29)") (class "Default")
      (node (ref "U300") (pin "29") (pinfunction "P2.3/TA2.0_29") (pintype "bidirectional"))
    )
    (net (code "57") (name "unconnected-(U300-P2.4{slash}TA2.1-Pad30)") (class "Default")
      (node (ref "U300") (pin "30") (pinfunction "P2.4/TA2.1_30") (pintype "bidirectional"))
    )
    (net (code "58") (name "unconnected-(U300-P2.6{slash}RTCCLK{slash}DMAE0-Pad32)") (class "Default")
      (node (ref "U300") (pin "32") (pinfunction "P2.6/RTCCLK/DMAE0_32") (pintype "bidirectional"))
    )
    (net (code "59") (name "unconnected-(U300-P2.7{slash}UCB0STE{slash}UCA0CLK-Pad33)") (class "Default")
      (node (ref "U300") (pin "33") (pinfunction "P2.7/UCB0STE/UCA0CLK_33") (pintype "bidirectional"))
    )
    (net (code "60") (name "unconnected-(U300-P3.2{slash}UCB0CLK{slash}UCA0STE-Pad36)") (class "Default")
      (node (ref "U300") (pin "36") (pinfunction "P3.2/UCB0CLK/UCA0STE_36") (pintype "bidirectional"))
    )
    (net (code "61") (name "unconnected-(U300-P4.0{slash}PM_UCB1STE{slash}PM_UCA1CLK-Pad41)") (class "Default")
      (node (ref "U300") (pin "41") (pinfunction "P4.0/PM_UCB1STE/PM_UCA1CLK_41") (pintype "bidirectional"))
    )
    (net (code "62") (name "unconnected-(U300-P4.1{slash}PM_UCB1SIMO{slash}PM_UCB1SDA-Pad42)") (class "Default")
      (node (ref "U300") (pin "42") (pinfunction "P4.1/PM_UCB1SIMO/PM_UCB1SDA_42") (pintype "bidirectional"))
    )
    (net (code "63") (name "unconnected-(U300-P4.2{slash}PM_UCB1SOMI{slash}PM_UCB1SCL-Pad43)") (class "Default")
      (node (ref "U300") (pin "43") (pinfunction "P4.2/PM_UCB1SOMI/PM_UCB1SCL_43") (pintype "bidirectional"))
    )
    (net (code "64") (name "unconnected-(U300-P4.3{slash}PM_UCB1CLK{slash}PM_UCA1STE-Pad44)") (class "Default")
      (node (ref "U300") (pin "44") (pinfunction "P4.3/PM_UCB1CLK/PM_UCA1STE_44") (pintype "bidirectional"))
    )
    (net (code "65") (name "unconnected-(U300-P4.4{slash}PM_UCA1TXD{slash}PM_UCA1SIMO-Pad45)") (class "Default")
      (node (ref "U300") (pin "45") (pinfunction "P4.4/PM_UCA1TXD/PM_UCA1SIMO_45") (pintype "bidirectional"))
    )
    (net (code "66") (name "unconnected-(U300-P4.5{slash}PM_UCA1RXD{slash}PM_UCA1SOMI-Pad46)") (class "Default")
      (node (ref "U300") (pin "46") (pinfunction "P4.5/PM_UCA1RXD/PM_UCA1SOMI_46") (pintype "bidirectional"))
    )
    (net (code "67") (name "unconnected-(U300-P4.6{slash}PM_NONE-Pad47)") (class "Default")
      (node (ref "U300") (pin "47") (pinfunction "P4.6/PM_NONE_47") (pintype "bidirectional"))
    )
    (net (code "68") (name "unconnected-(U300-P4.7{slash}PM_NONE-Pad48)") (class "Default")
      (node (ref "U300") (pin "48") (pinfunction "P4.7/PM_NONE_48") (pintype "bidirectional"))
    )
    (net (code "69") (name "unconnected-(U300-P5.0{slash}A8{slash}VREF+{slash}VEREF+-Pad9)") (class "Default")
      (node (ref "U300") (pin "9") (pinfunction "P5.0/A8/VREF+/VEREF+_9") (pintype "bidirectional"))
    )
    (net (code "70") (name "unconnected-(U300-P5.1{slash}A9{slash}VREF-{slash}VEREF--Pad10)") (class "Default")
      (node (ref "U300") (pin "10") (pinfunction "P5.1/A9/VREF-/VEREF-_10") (pintype "bidirectional"))
    )
    (net (code "71") (name "unconnected-(U300-P5.4{slash}XIN-Pad12)") (class "Default")
      (node (ref "U300") (pin "12") (pinfunction "P5.4/XIN_12") (pintype "bidirectional"))
    )
    (net (code "72") (name "unconnected-(U300-P5.5{slash}XOUT-Pad13)") (class "Default")
      (node (ref "U300") (pin "13") (pinfunction "P5.5/XOUT_13") (pintype "bidirectional"))
    )
    (net (code "73") (name "unconnected-(U300-P6.0{slash}CB0{slash}A0-Pad1)") (class "Default")
      (node (ref "U300") (pin "1") (pinfunction "P6.0/CB0/A0_1") (pintype "bidirectional"))
    )
    (net (code "74") (name "unconnected-(U300-P6.1{slash}CB1{slash}A1-Pad2)") (class "Default")
      (node (ref "U300") (pin "2") (pinfunction "P6.1/CB1/A1_2") (pintype "bidirectional"))
    )
    (net (code "75") (name "unconnected-(U300-P6.2{slash}CB2{slash}A2-Pad3)") (class "Default")
      (node (ref "U300") (pin "3") (pinfunction "P6.2/CB2/A2_3") (pintype "bidirectional"))
    )
    (net (code "76") (name "unconnected-(U300-P6.3{slash}CB3{slash}A3-Pad4)") (class "Default")
      (node (ref "U300") (pin "4") (pinfunction "P6.3/CB3/A3_4") (pintype "bidirectional"))
    )
    (net (code "77") (name "unconnected-(U300-P6.4{slash}CB4{slash}A4-Pad5)") (class "Default")
      (node (ref "U300") (pin "5") (pinfunction "P6.4/CB4/A4_5") (pintype "bidirectional"))
    )
    (net (code "78") (name "unconnected-(U300-P6.5{slash}CB5{slash}A5-Pad6)") (class "Default")
      (node (ref "U300") (pin "6") (pinfunction "P6.5/CB5/A5_6") (pintype "bidirectional"))
    )
    (net (code "79") (name "unconnected-(U300-P6.6{slash}CB6{slash}A6-Pad7)") (class "Default")
      (node (ref "U300") (pin "7") (pinfunction "P6.6/CB6/A6_7") (pintype "bidirectional"))
    )
    (net (code "80") (name "unconnected-(U300-P6.7{slash}CB7{slash}A7-Pad8)") (class "Default")
      (node (ref "U300") (pin "8") (pinfunction "P6.7/CB7/A7_8") (pintype "bidirectional"))
    )
  )
)
